# 3hub.net
KiCad netlist of a schematic drawn in EAGLE
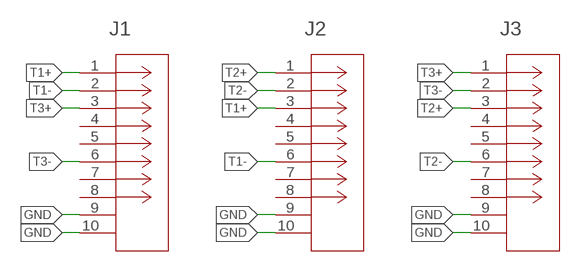
[diagram p0: schematic, sheet 1]

(export (version "E")
  (design (tool "Eeschema 10.0.6"))
  (components
    (comp (ref "J1")
      (value "1-406541-1")
      (footprint "eagle-import:CONN8_406541_TEC")
      (fields (field (name "COPYRIGHT") "Copyright (C) 2021 Ultra Librarian. All rights reserved."))
      (libsource (lib "eagle-import") (part "1-406541-1"))
    )
    (comp (ref "J2")
      (value "1-406541-1")
      (footprint "eagle-import:CONN8_406541_TEC")
      (fields (field (name "COPYRIGHT") "Copyright (C) 2021 Ultra Librarian. All rights reserved."))
      (libsource (lib "eagle-import") (part "1-406541-1"))
    )
    (comp (ref "J3")
      (value "1-406541-1")
      (footprint "eagle-import:CONN8_406541_TEC")
      (fields (field (name "COPYRIGHT") "Copyright (C) 2021 Ultra Librarian. All rights reserved."))
      (libsource (lib "eagle-import") (part "1-406541-1"))
    )
  )
  (nets
    (net (code "1") (name "GND") (class "Default")
      (node (ref "J1") (pin "10") (pinfunction "10_10") (pintype "passive"))
      (node (ref "J1") (pin "9") (pinfunction "9_9") (pintype "passive"))
      (node (ref "J2") (pin "10") (pinfunction "10_10") (pintype "passive"))
      (node (ref "J2") (pin "9") (pinfunction "9_9") (pintype "passive"))
      (node (ref "J3") (pin "10") (pinfunction "10_10") (pintype "passive"))
      (node (ref "J3") (pin "9") (pinfunction "9_9") (pintype "passive"))
    )
    (net (code "2") (name "T1+") (class "Default")
      (node (ref "J1") (pin "1") (pinfunction "1_1") (pintype "passive"))
      (node (ref "J2") (pin "3") (pinfunction "3_3") (pintype "passive"))
    )
    (net (code "3") (name "T1-") (class "Default")
      (node (ref "J1") (pin "2") (pinfunction "2_2") (pintype "passive"))
      (node (ref "J2") (pin "6") (pinfunction "6_6") (pintype "passive"))
    )
    (net (code "4") (name "T2+") (class "Default")
      (node (ref "J2") (pin "1") (pinfunction "1_1") (pintype "passive"))
      (node (ref "J3") (pin "3") (pinfunction "3_3") (pintype "passive"))
    )
    (net (code "5") (name "T2-") (class "Default")
      (node (ref "J2") (pin "2") (pinfunction "2_2") (pintype "passive"))
      (node (ref "J3") (pin "6") (pinfunction "6_6") (pintype "passive"))
    )
    (net (code "6") (name "T3+") (class "Default")
      (node (ref "J1") (pin "3") (pinfunction "3_3") (pintype "passive"))
      (node (ref "J3") (pin "1") (pinfunction "1_1") (pintype "passive"))
    )
    (net (code "7") (name "T3-") (class "Default")
      (node (ref "J1") (pin "6") (pinfunction "6_6") (pintype "passive"))
      (node (ref "J3") (pin "2") (pinfunction "2_2") (pintype "passive"))
    )
    (net (code "8") (name "unconnected-(J1-Pad4)") (class "Default")
      (node (ref "J1") (pin "4") (pinfunction "4_4") (pintype "passive"))
    )
    (net (code "9") (name "unconnected-(J1-Pad5)") (class "Default")
      (node (ref "J1") (pin "5") (pinfunction "5_5") (pintype "passive"))
    )
    (net (code "10") (name "unconnected-(J1-Pad7)") (class "Default")
      (node (ref "J1") (pin "7") (pinfunction "7_7") (pintype "passive"))
    )
    (net (code "11") (name "unconnected-(J1-Pad8)") (class "Default")
      (node (ref "J1") (pin "8") (pinfunction "8_8") (pintype "passive"))
    )
    (net (code "12") (name "unconnected-(J2-Pad4)") (class "Default")
      (node (ref "J2") (pin "4") (pinfunction "4_4") (pintype "passive"))
    )
    (net (code "13") (name "unconnected-(J2-Pad5)") (class "Default")
      (node (ref "J2") (pin "5") (pinfunction "5_5") (pintype "passive"))
    )
    (net (code "14") (name "unconnected-(J2-Pad7)") (class "Default")
      (node (ref "J2") (pin "7") (pinfunction "7_7") (pintype "passive"))
    )
    (net (code "15") (name "unconnected-(J2-Pad8)") (class "Default")
      (node (ref "J2") (pin "8") (pinfunction "8_8") (pintype "passive"))
    )
    (net (code "16") (name "unconnected-(J3-Pad4)") (class "Default")
      (node (ref "J3") (pin "4") (pinfunction "4_4") (pintype "passive"))
    )
    (net (code "17") (name "unconnected-(J3-Pad5)") (class "Default")
      (node (ref "J3") (pin "5") (pinfunction "5_5") (pintype "passive"))
    )
    (net (code "18") (name "unconnected-(J3-Pad7)") (class "Default")
      (node (ref "J3") (pin "7") (pinfunction "7_7") (pintype "passive"))
    )
    (net (code "19") (name "unconnected-(J3-Pad8)") (class "Default")
      (node (ref "J3") (pin "8") (pinfunction "8_8") (pintype "passive"))
    )
  )
)
